# 328P_ISP.net
KiCad netlist of a schematic drawn in EAGLE
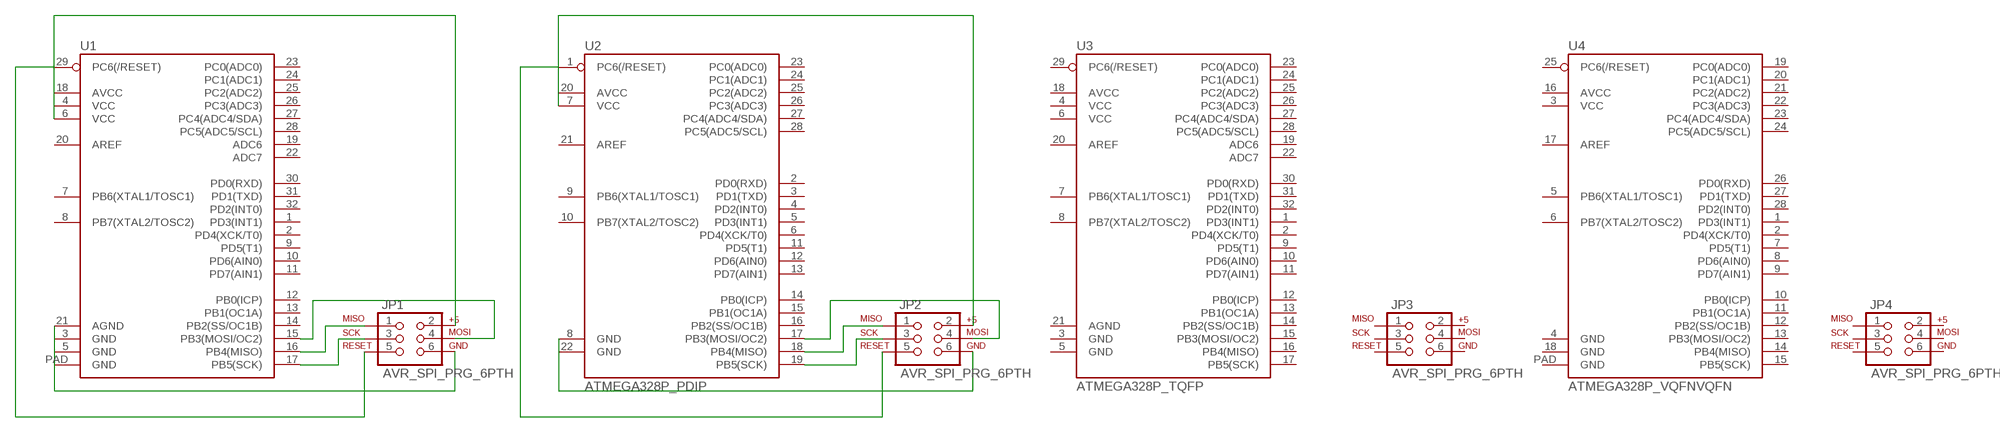
[diagram p0: schematic, sheet 1]

(export (version "E")
  (design (tool "Eeschema 10.0.6"))
  (components
    (comp (ref "JP1")
      (value "AVR_SPI_PRG_6PTH")
      (footprint "eagle-import:2X3")
      (libsource (lib "eagle-import") (part "AVR_SPI_PRG_6PTH"))
    )
    (comp (ref "JP2")
      (value "AVR_SPI_PRG_6PTH")
      (footprint "eagle-import:2X3")
      (libsource (lib "eagle-import") (part "AVR_SPI_PRG_6PTH"))
    )
    (comp (ref "JP3")
      (value "AVR_SPI_PRG_6PTH")
      (footprint "eagle-import:2X3")
      (libsource (lib "eagle-import") (part "AVR_SPI_PRG_6PTH"))
    )
    (comp (ref "JP4")
      (value "AVR_SPI_PRG_6PTH")
      (footprint "eagle-import:2X3")
      (libsource (lib "eagle-import") (part "AVR_SPI_PRG_6PTH"))
    )
    (comp (ref "U1")
      (value "ATMEGA328P_MLFMLF32")
      (footprint "eagle-import:MLF32-PAD")
      (libsource (lib "eagle-import") (part "ATMEGA328P_MLFMLF32"))
    )
    (comp (ref "U2")
      (value "ATMEGA328P_PDIP")
      (footprint "eagle-import:DIL28-3")
      (libsource (lib "eagle-import") (part "ATMEGA328P_PDIP"))
    )
    (comp (ref "U3")
      (value "ATMEGA328P_TQFP")
      (footprint "eagle-import:TQFP32-08")
      (libsource (lib "eagle-import") (part "ATMEGA328P_TQFP"))
    )
    (comp (ref "U4")
      (value "ATMEGA328P_VQFNVQFN")
      (footprint "eagle-import:VQFN-28")
      (libsource (lib "eagle-import") (part "ATMEGA328P_VQFNVQFN"))
    )
  )
  (nets
    (net (code "1") (name "Net-(JP2-Pad6)") (class "Default")
      (node (ref "JP2") (pin "6") (pinfunction "6_6") (pintype "passive"))
      (node (ref "U2") (pin "22") (pinfunction "GND_22") (pintype "bidirectional"))
      (node (ref "U2") (pin "8") (pinfunction "GND_8") (pintype "bidirectional"))
    )
    (net (code "2") (name "Net-(U1-AGND)") (class "Default")
      (node (ref "JP1") (pin "6") (pinfunction "6_6") (pintype "passive"))
      (node (ref "U1") (pin "21") (pinfunction "AGND_21") (pintype "bidirectional"))
      (node (ref "U1") (pin "3") (pinfunction "GND_3") (pintype "bidirectional"))
      (node (ref "U1") (pin "5") (pinfunction "GND_5") (pintype "bidirectional"))
      (node (ref "U1") (pin "PAD") (pinfunction "GND_PAD") (pintype "bidirectional"))
    )
    (net (code "3") (name "Net-(U1-AVCC)") (class "Default")
      (node (ref "JP1") (pin "2") (pinfunction "2_2") (pintype "passive"))
      (node (ref "U1") (pin "18") (pinfunction "AVCC_18") (pintype "bidirectional"))
      (node (ref "U1") (pin "4") (pinfunction "VCC_4") (pintype "bidirectional"))
      (node (ref "U1") (pin "6") (pinfunction "VCC_6") (pintype "bidirectional"))
    )
    (net (code "4") (name "Net-(U1-PB3(MOSI{slash}OC2))") (class "Default")
      (node (ref "JP1") (pin "4") (pinfunction "4_4") (pintype "passive"))
      (node (ref "U1") (pin "15") (pinfunction "PB3(MOSI/OC2)_15") (pintype "bidirectional"))
    )
    (net (code "5") (name "Net-(U1-PB4(MISO))") (class "Default")
      (node (ref "JP1") (pin "1") (pinfunction "1_1") (pintype "passive"))
      (node (ref "U1") (pin "16") (pinfunction "PB4(MISO)_16") (pintype "bidirectional"))
    )
    (net (code "6") (name "Net-(U1-PB5(SCK))") (class "Default")
      (node (ref "JP1") (pin "3") (pinfunction "3_3") (pintype "passive"))
      (node (ref "U1") (pin "17") (pinfunction "PB5(SCK)_17") (pintype "bidirectional"))
    )
    (net (code "7") (name "Net-(U1-PC6({slash}RESET))") (class "Default")
      (node (ref "JP1") (pin "5") (pinfunction "5_5") (pintype "passive"))
      (node (ref "U1") (pin "29") (pinfunction "PC6(/RESET)_29") (pintype "bidirectional"))
    )
    (net (code "8") (name "Net-(U2-AVCC)") (class "Default")
      (node (ref "JP2") (pin "2") (pinfunction "2_2") (pintype "passive"))
      (node (ref "U2") (pin "20") (pinfunction "AVCC_20") (pintype "bidirectional"))
      (node (ref "U2") (pin "7") (pinfunction "VCC_7") (pintype "bidirectional"))
    )
    (net (code "9") (name "Net-(U2-PB3(MOSI{slash}OC2))") (class "Default")
      (node (ref "JP2") (pin "4") (pinfunction "4_4") (pintype "passive"))
      (node (ref "U2") (pin "17") (pinfunction "PB3(MOSI/OC2)_17") (pintype "bidirectional"))
    )
    (net (code "10") (name "Net-(U2-PB4(MISO))") (class "Default")
      (node (ref "JP2") (pin "1") (pinfunction "1_1") (pintype "passive"))
      (node (ref "U2") (pin "18") (pinfunction "PB4(MISO)_18") (pintype "bidirectional"))
    )
    (net (code "11") (name "Net-(U2-PB5(SCK))") (class "Default")
      (node (ref "JP2") (pin "3") (pinfunction "3_3") (pintype "passive"))
      (node (ref "U2") (pin "19") (pinfunction "PB5(SCK)_19") (pintype "bidirectional"))
    )
    (net (code "12") (name "Net-(U2-PC6({slash}RESET))") (class "Default")
      (node (ref "JP2") (pin "5") (pinfunction "5_5") (pintype "passive"))
      (node (ref "U2") (pin "1") (pinfunction "PC6(/RESET)_1") (pintype "bidirectional"))
    )
    (net (code "13") (name "unconnected-(JP3-Pad1)") (class "Default")
      (node (ref "JP3") (pin "1") (pinfunction "1_1") (pintype "passive"))
    )
    (net (code "14") (name "unconnected-(JP3-Pad2)") (class "Default")
      (node (ref "JP3") (pin "2") (pinfunction "2_2") (pintype "passive"))
    )
    (net (code "15") (name "unconnected-(JP3-Pad3)") (class "Default")
      (node (ref "JP3") (pin "3") (pinfunction "3_3") (pintype "passive"))
    )
    (net (code "16") (name "unconnected-(JP3-Pad4)") (class "Default")
      (node (ref "JP3") (pin "4") (pinfunction "4_4") (pintype "passive"))
    )
    (net (code "17") (name "unconnected-(JP3-Pad5)") (class "Default")
      (node (ref "JP3") (pin "5") (pinfunction "5_5") (pintype "passive"))
    )
    (net (code "18") (name "unconnected-(JP3-Pad6)") (class "Default")
      (node (ref "JP3") (pin "6") (pinfunction "6_6") (pintype "passive"))
    )
    (net (code "19") (name "unconnected-(JP4-Pad1)") (class "Default")
      (node (ref "JP4") (pin "1") (pinfunction "1_1") (pintype "passive"))
    )
    (net (code "20") (name "unconnected-(JP4-Pad2)") (class "Default")
      (node (ref "JP4") (pin "2") (pinfunction "2_2") (pintype "passive"))
    )
    (net (code "21") (name "unconnected-(JP4-Pad3)") (class "Default")
      (node (ref "JP4") (pin "3") (pinfunction "3_3") (pintype "passive"))
    )
    (net (code "22") (name "unconnected-(JP4-Pad4)") (class "Default")
      (node (ref "JP4") (pin "4") (pinfunction "4_4") (pintype "passive"))
    )
    (net (code "23") (name "unconnected-(JP4-Pad5)") (class "Default")
      (node (ref "JP4") (pin "5") (pinfunction "5_5") (pintype "passive"))
    )
    (net (code "24") (name "unconnected-(JP4-Pad6)") (class "Default")
      (node (ref "JP4") (pin "6") (pinfunction "6_6") (pintype "passive"))
    )
    (net (code "25") (name "unconnected-(U1-ADC6-Pad19)") (class "Default")
      (node (ref "U1") (pin "19") (pinfunction "ADC6_19") (pintype "bidirectional"))
    )
    (net (code "26") (name "unconnected-(U1-ADC7-Pad22)") (class "Default")
      (node (ref "U1") (pin "22") (pinfunction "ADC7_22") (pintype "bidirectional"))
    )
    (net (code "27") (name "unconnected-(U1-AREF-Pad20)") (class "Default")
      (node (ref "U1") (pin "20") (pinfunction "AREF_20") (pintype "bidirectional"))
    )
    (net (code "28") (name "unconnected-(U1-PB0(ICP)-Pad12)") (class "Default")
      (node (ref "U1") (pin "12") (pinfunction "PB0(ICP)_12") (pintype "bidirectional"))
    )
    (net (code "29") (name "unconnected-(U1-PB1(OC1A)-Pad13)") (class "Default")
      (node (ref "U1") (pin "13") (pinfunction "PB1(OC1A)_13") (pintype "bidirectional"))
    )
    (net (code "30") (name "unconnected-(U1-PB2(SS{slash}OC1B)-Pad14)") (class "Default")
      (node (ref "U1") (pin "14") (pinfunction "PB2(SS/OC1B)_14") (pintype "bidirectional"))
    )
    (net (code "31") (name "unconnected-(U1-PB6(XTAL1{slash}TOSC1)-Pad7)") (class "Default")
      (node (ref "U1") (pin "7") (pinfunction "PB6(XTAL1/TOSC1)_7") (pintype "bidirectional"))
    )
    (net (code "32") (name "unconnected-(U1-PB7(XTAL2{slash}TOSC2)-Pad8)") (class "Default")
      (node (ref "U1") (pin "8") (pinfunction "PB7(XTAL2/TOSC2)_8") (pintype "bidirectional"))
    )
    (net (code "33") (name "unconnected-(U1-PC0(ADC0)-Pad23)") (class "Default")
      (node (ref "U1") (pin "23") (pinfunction "PC0(ADC0)_23") (pintype "bidirectional"))
    )
    (net (code "34") (name "unconnected-(U1-PC1(ADC1)-Pad24)") (class "Default")
      (node (ref "U1") (pin "24") (pinfunction "PC1(ADC1)_24") (pintype "bidirectional"))
    )
    (net (code "35") (name "unconnected-(U1-PC2(ADC2)-Pad25)") (class "Default")
      (node (ref "U1") (pin "25") (pinfunction "PC2(ADC2)_25") (pintype "bidirectional"))
    )
    (net (code "36") (name "unconnected-(U1-PC3(ADC3)-Pad26)") (class "Default")
      (node (ref "U1") (pin "26") (pinfunction "PC3(ADC3)_26") (pintype "bidirectional"))
    )
    (net (code "37") (name "unconnected-(U1-PC4(ADC4{slash}SDA)-Pad27)") (class "Default")
      (node (ref "U1") (pin "27") (pinfunction "PC4(ADC4/SDA)_27") (pintype "bidirectional"))
    )
    (net (code "38") (name "unconnected-(U1-PC5(ADC5{slash}SCL)-Pad28)") (class "Default")
      (node (ref "U1") (pin "28") (pinfunction "PC5(ADC5/SCL)_28") (pintype "bidirectional"))
    )
    (net (code "39") (name "unconnected-(U1-PD0(RXD)-Pad30)") (class "Default")
      (node (ref "U1") (pin "30") (pinfunction "PD0(RXD)_30") (pintype "bidirectional"))
    )
    (net (code "40") (name "unconnected-(U1-PD1(TXD)-Pad31)") (class "Default")
      (node (ref "U1") (pin "31") (pinfunction "PD1(TXD)_31") (pintype "bidirectional"))
    )
    (net (code "41") (name "unconnected-(U1-PD2(INT0)-Pad32)") (class "Default")
      (node (ref "U1") (pin "32") (pinfunction "PD2(INT0)_32") (pintype "bidirectional"))
    )
    (net (code "42") (name "unconnected-(U1-PD3(INT1)-Pad1)") (class "Default")
      (node (ref "U1") (pin "1") (pinfunction "PD3(INT1)_1") (pintype "bidirectional"))
    )
    (net (code "43") (name "unconnected-(U1-PD4(XCK{slash}T0)-Pad2)") (class "Default")
      (node (ref "U1") (pin "2") (pinfunction "PD4(XCK/T0)_2") (pintype "bidirectional"))
    )
    (net (code "44") (name "unconnected-(U1-PD5(T1)-Pad9)") (class "Default")
      (node (ref "U1") (pin "9") (pinfunction "PD5(T1)_9") (pintype "bidirectional"))
    )
    (net (code "45") (name "unconnected-(U1-PD6(AIN0)-Pad10)") (class "Default")
      (node (ref "U1") (pin "10") (pinfunction "PD6(AIN0)_10") (pintype "bidirectional"))
    )
    (net (code "46") (name "unconnected-(U1-PD7(AIN1)-Pad11)") (class "Default")
      (node (ref "U1") (pin "11") (pinfunction "PD7(AIN1)_11") (pintype "bidirectional"))
    )
    (net (code "47") (name "unconnected-(U2-AREF-Pad21)") (class "Default")
      (node (ref "U2") (pin "21") (pinfunction "AREF_21") (pintype "bidirectional"))
    )
    (net (code "48") (name "unconnected-(U2-PB0(ICP)-Pad14)") (class "Default")
      (node (ref "U2") (pin "14") (pinfunction "PB0(ICP)_14") (pintype "bidirectional"))
    )
    (net (code "49") (name "unconnected-(U2-PB1(OC1A)-Pad15)") (class "Default")
      (node (ref "U2") (pin "15") (pinfunction "PB1(OC1A)_15") (pintype "bidirectional"))
    )
    (net (code "50") (name "unconnected-(U2-PB2(SS{slash}OC1B)-Pad16)") (class "Default")
      (node (ref "U2") (pin "16") (pinfunction "PB2(SS/OC1B)_16") (pintype "bidirectional"))
    )
    (net (code "51") (name "unconnected-(U2-PB6(XTAL1{slash}TOSC1)-Pad9)") (class "Default")
      (node (ref "U2") (pin "9") (pinfunction "PB6(XTAL1/TOSC1)_9") (pintype "bidirectional"))
    )
    (net (code "52") (name "unconnected-(U2-PB7(XTAL2{slash}TOSC2)-Pad10)") (class "Default")
      (node (ref "U2") (pin "10") (pinfunction "PB7(XTAL2/TOSC2)_10") (pintype "bidirectional"))
    )
    (net (code "53") (name "unconnected-(U2-PC0(ADC0)-Pad23)") (class "Default")
      (node (ref "U2") (pin "23") (pinfunction "PC0(ADC0)_23") (pintype "bidirectional"))
    )
    (net (code "54") (name "unconnected-(U2-PC1(ADC1)-Pad24)") (class "Default")
      (node (ref "U2") (pin "24") (pinfunction "PC1(ADC1)_24") (pintype "bidirectional"))
    )
    (net (code "55") (name "unconnected-(U2-PC2(ADC2)-Pad25)") (class "Default")
      (node (ref "U2") (pin "25") (pinfunction "PC2(ADC2)_25") (pintype "bidirectional"))
    )
    (net (code "56") (name "unconnected-(U2-PC3(ADC3)-Pad26)") (class "Default")
      (node (ref "U2") (pin "26") (pinfunction "PC3(ADC3)_26") (pintype "bidirectional"))
    )
    (net (code "57") (name "unconnected-(U2-PC4(ADC4{slash}SDA)-Pad27)") (class "Default")
      (node (ref "U2") (pin "27") (pinfunction "PC4(ADC4/SDA)_27") (pintype "bidirectional"))
    )
    (net (code "58") (name "unconnected-(U2-PC5(ADC5{slash}SCL)-Pad28)") (class "Default")
      (node (ref "U2") (pin "28") (pinfunction "PC5(ADC5/SCL)_28") (pintype "bidirectional"))
    )
    (net (code "59") (name "unconnected-(U2-PD0(RXD)-Pad2)") (class "Default")
      (node (ref "U2") (pin "2") (pinfunction "PD0(RXD)_2") (pintype "bidirectional"))
    )
    (net (code "60") (name "unconnected-(U2-PD1(TXD)-Pad3)") (class "Default")
      (node (ref "U2") (pin "3") (pinfunction "PD1(TXD)_3") (pintype "bidirectional"))
    )
    (net (code "61") (name "unconnected-(U2-PD2(INT0)-Pad4)") (class "Default")
      (node (ref "U2") (pin "4") (pinfunction "PD2(INT0)_4") (pintype "bidirectional"))
    )
    (net (code "62") (name "unconnected-(U2-PD3(INT1)-Pad5)") (class "Default")
      (node (ref "U2") (pin "5") (pinfunction "PD3(INT1)_5") (pintype "bidirectional"))
    )
    (net (code "63") (name "unconnected-(U2-PD4(XCK{slash}T0)-Pad6)") (class "Default")
      (node (ref "U2") (pin "6") (pinfunction "PD4(XCK/T0)_6") (pintype "bidirectional"))
    )
    (net (code "64") (name "unconnected-(U2-PD5(T1)-Pad11)") (class "Default")
      (node (ref "U2") (pin "11") (pinfunction "PD5(T1)_11") (pintype "bidirectional"))
    )
    (net (code "65") (name "unconnected-(U2-PD6(AIN0)-Pad12)") (class "Default")
      (node (ref "U2") (pin "12") (pinfunction "PD6(AIN0)_12") (pintype "bidirectional"))
    )
    (net (code "66") (name "unconnected-(U2-PD7(AIN1)-Pad13)") (class "Default")
      (node (ref "U2") (pin "13") (pinfunction "PD7(AIN1)_13") (pintype "bidirectional"))
    )
    (net (code "67") (name "unconnected-(U3-ADC6-Pad19)") (class "Default")
      (node (ref "U3") (pin "19") (pinfunction "ADC6_19") (pintype "bidirectional"))
    )
    (net (code "68") (name "unconnected-(U3-ADC7-Pad22)") (class "Default")
      (node (ref "U3") (pin "22") (pinfunction "ADC7_22") (pintype "bidirectional"))
    )
    (net (code "69") (name "unconnected-(U3-AGND-Pad21)") (class "Default")
      (node (ref "U3") (pin "21") (pinfunction "AGND_21") (pintype "bidirectional"))
    )
    (net (code "70") (name "unconnected-(U3-AREF-Pad20)") (class "Default")
      (node (ref "U3") (pin "20") (pinfunction "AREF_20") (pintype "bidirectional"))
    )
    (net (code "71") (name "unconnected-(U3-AVCC-Pad18)") (class "Default")
      (node (ref "U3") (pin "18") (pinfunction "AVCC_18") (pintype "bidirectional"))
    )
    (net (code "72") (name "unconnected-(U3-GND-Pad3)") (class "Default")
      (node (ref "U3") (pin "3") (pinfunction "GND_3") (pintype "bidirectional"))
    )
    (net (code "73") (name "unconnected-(U3-GND-Pad5)") (class "Default")
      (node (ref "U3") (pin "5") (pinfunction "GND_5") (pintype "bidirectional"))
    )
    (net (code "74") (name "unconnected-(U3-PB0(ICP)-Pad12)") (class "Default")
      (node (ref "U3") (pin "12") (pinfunction "PB0(ICP)_12") (pintype "bidirectional"))
    )
    (net (code "75") (name "unconnected-(U3-PB1(OC1A)-Pad13)") (class "Default")
      (node (ref "U3") (pin "13") (pinfunction "PB1(OC1A)_13") (pintype "bidirectional"))
    )
    (net (code "76") (name "unconnected-(U3-PB2(SS{slash}OC1B)-Pad14)") (class "Default")
      (node (ref "U3") (pin "14") (pinfunction "PB2(SS/OC1B)_14") (pintype "bidirectional"))
    )
    (net (code "77") (name "unconnected-(U3-PB3(MOSI{slash}OC2)-Pad15)") (class "Default")
      (node (ref "U3") (pin "15") (pinfunction "PB3(MOSI/OC2)_15") (pintype "bidirectional"))
    )
    (net (code "78") (name "unconnected-(U3-PB4(MISO)-Pad16)") (class "Default")
      (node (ref "U3") (pin "16") (pinfunction "PB4(MISO)_16") (pintype "bidirectional"))
    )
    (net (code "79") (name "unconnected-(U3-PB5(SCK)-Pad17)") (class "Default")
      (node (ref "U3") (pin "17") (pinfunction "PB5(SCK)_17") (pintype "bidirectional"))
    )
    (net (code "80") (name "unconnected-(U3-PB6(XTAL1{slash}TOSC1)-Pad7)") (class "Default")
      (node (ref "U3") (pin "7") (pinfunction "PB6(XTAL1/TOSC1)_7") (pintype "bidirectional"))
    )
    (net (code "81") (name "unconnected-(U3-PB7(XTAL2{slash}TOSC2)-Pad8)") (class "Default")
      (node (ref "U3") (pin "8") (pinfunction "PB7(XTAL2/TOSC2)_8") (pintype "bidirectional"))
    )
    (net (code "82") (name "unconnected-(U3-PC0(ADC0)-Pad23)") (class "Default")
      (node (ref "U3") (pin "23") (pinfunction "PC0(ADC0)_23") (pintype "bidirectional"))
    )
    (net (code "83") (name "unconnected-(U3-PC1(ADC1)-Pad24)") (class "Default")
      (node (ref "U3") (pin "24") (pinfunction "PC1(ADC1)_24") (pintype "bidirectional"))
    )
    (net (code "84") (name "unconnected-(U3-PC2(ADC2)-Pad25)") (class "Default")
      (node (ref "U3") (pin "25") (pinfunction "PC2(ADC2)_25") (pintype "bidirectional"))
    )
    (net (code "85") (name "unconnected-(U3-PC3(ADC3)-Pad26)") (class "Default")
      (node (ref "U3") (pin "26") (pinfunction "PC3(ADC3)_26") (pintype "bidirectional"))
    )
    (net (code "86") (name "unconnected-(U3-PC4(ADC4{slash}SDA)-Pad27)") (class "Default")
      (node (ref "U3") (pin "27") (pinfunction "PC4(ADC4/SDA)_27") (pintype "bidirectional"))
    )
    (net (code "87") (name "unconnected-(U3-PC5(ADC5{slash}SCL)-Pad28)") (class "Default")
      (node (ref "U3") (pin "28") (pinfunction "PC5(ADC5/SCL)_28") (pintype "bidirectional"))
    )
    (net (code "88") (name "unconnected-(U3-PC6({slash}RESET)-Pad29)") (class "Default")
      (node (ref "U3") (pin "29") (pinfunction "PC6(/RESET)_29") (pintype "bidirectional"))
    )
    (net (code "89") (name "unconnected-(U3-PD0(RXD)-Pad30)") (class "Default")
      (node (ref "U3") (pin "30") (pinfunction "PD0(RXD)_30") (pintype "bidirectional"))
    )
    (net (code "90") (name "unconnected-(U3-PD1(TXD)-Pad31)") (class "Default")
      (node (ref "U3") (pin "31") (pinfunction "PD1(TXD)_31") (pintype "bidirectional"))
    )
    (net (code "91") (name "unconnected-(U3-PD2(INT0)-Pad32)") (class "Default")
      (node (ref "U3") (pin "32") (pinfunction "PD2(INT0)_32") (pintype "bidirectional"))
    )
    (net (code "92") (name "unconnected-(U3-PD3(INT1)-Pad1)") (class "Default")
      (node (ref "U3") (pin "1") (pinfunction "PD3(INT1)_1") (pintype "bidirectional"))
    )
    (net (code "93") (name "unconnected-(U3-PD4(XCK{slash}T0)-Pad2)") (class "Default")
      (node (ref "U3") (pin "2") (pinfunction "PD4(XCK/T0)_2") (pintype "bidirectional"))
    )
    (net (code "94") (name "unconnected-(U3-PD5(T1)-Pad9)") (class "Default")
      (node (ref "U3") (pin "9") (pinfunction "PD5(T1)_9") (pintype "bidirectional"))
    )
    (net (code "95") (name "unconnected-(U3-PD6(AIN0)-Pad10)") (class "Default")
      (node (ref "U3") (pin "10") (pinfunction "PD6(AIN0)_10") (pintype "bidirectional"))
    )
    (net (code "96") (name "unconnected-(U3-PD7(AIN1)-Pad11)") (class "Default")
      (node (ref "U3") (pin "11") (pinfunction "PD7(AIN1)_11") (pintype "bidirectional"))
    )
    (net (code "97") (name "unconnected-(U3-VCC-Pad4)") (class "Default")
      (node (ref "U3") (pin "4") (pinfunction "VCC_4") (pintype "bidirectional"))
    )
    (net (code "98") (name "unconnected-(U3-VCC-Pad6)") (class "Default")
      (node (ref "U3") (pin "6") (pinfunction "VCC_6") (pintype "bidirectional"))
    )
    (net (code "99") (name "unconnected-(U4-AREF-Pad17)") (class "Default")
      (node (ref "U4") (pin "17") (pinfunction "AREF_17") (pintype "bidirectional"))
    )
    (net (code "100") (name "unconnected-(U4-AVCC-Pad16)") (class "Default")
      (node (ref "U4") (pin "16") (pinfunction "AVCC_16") (pintype "bidirectional"))
    )
    (net (code "101") (name "unconnected-(U4-GND-Pad4)") (class "Default")
      (node (ref "U4") (pin "4") (pinfunction "GND_4") (pintype "bidirectional"))
    )
    (net (code "102") (name "unconnected-(U4-GND-Pad18)") (class "Default")
      (node (ref "U4") (pin "18") (pinfunction "GND_18") (pintype "bidirectional"))
    )
    (net (code "103") (name "unconnected-(U4-GND-PadPAD)") (class "Default")
      (node (ref "U4") (pin "PAD") (pinfunction "GND_PAD") (pintype "bidirectional"))
    )
    (net (code "104") (name "unconnected-(U4-PB0(ICP)-Pad10)") (class "Default")
      (node (ref "U4") (pin "10") (pinfunction "PB0(ICP)_10") (pintype "bidirectional"))
    )
    (net (code "105") (name "unconnected-(U4-PB1(OC1A)-Pad11)") (class "Default")
      (node (ref "U4") (pin "11") (pinfunction "PB1(OC1A)_11") (pintype "bidirectional"))
    )
    (net (code "106") (name "unconnected-(U4-PB2(SS{slash}OC1B)-Pad12)") (class "Default")
      (node (ref "U4") (pin "12") (pinfunction "PB2(SS/OC1B)_12") (pintype "bidirectional"))
    )
    (net (code "107") (name "unconnected-(U4-PB3(MOSI{slash}OC2)-Pad13)") (class "Default")
      (node (ref "U4") (pin "13") (pinfunction "PB3(MOSI/OC2)_13") (pintype "bidirectional"))
    )
    (net (code "108") (name "unconnected-(U4-PB4(MISO)-Pad14)") (class "Default")
      (node (ref "U4") (pin "14") (pinfunction "PB4(MISO)_14") (pintype "bidirectional"))
    )
    (net (code "109") (name "unconnected-(U4-PB5(SCK)-Pad15)") (class "Default")
      (node (ref "U4") (pin "15") (pinfunction "PB5(SCK)_15") (pintype "bidirectional"))
    )
    (net (code "110") (name "unconnected-(U4-PB6(XTAL1{slash}TOSC1)-Pad5)") (class "Default")
      (node (ref "U4") (pin "5") (pinfunction "PB6(XTAL1/TOSC1)_5") (pintype "bidirectional"))
    )
    (net (code "111") (name "unconnected-(U4-PB7(XTAL2{slash}TOSC2)-Pad6)") (class "Default")
      (node (ref "U4") (pin "6") (pinfunction "PB7(XTAL2/TOSC2)_6") (pintype "bidirectional"))
    )
    (net (code "112") (name "unconnected-(U4-PC0(ADC0)-Pad19)") (class "Default")
      (node (ref "U4") (pin "19") (pinfunction "PC0(ADC0)_19") (pintype "bidirectional"))
    )
    (net (code "113") (name "unconnected-(U4-PC1(ADC1)-Pad20)") (class "Default")
      (node (ref "U4") (pin "20") (pinfunction "PC1(ADC1)_20") (pintype "bidirectional"))
    )
    (net (code "114") (name "unconnected-(U4-PC2(ADC2)-Pad21)") (class "Default")
      (node (ref "U4") (pin "21") (pinfunction "PC2(ADC2)_21") (pintype "bidirectional"))
    )
    (net (code "115") (name "unconnected-(U4-PC3(ADC3)-Pad22)") (class "Default")
      (node (ref "U4") (pin "22") (pinfunction "PC3(ADC3)_22") (pintype "bidirectional"))
    )
    (net (code "116") (name "unconnected-(U4-PC4(ADC4{slash}SDA)-Pad23)") (class "Default")
      (node (ref "U4") (pin "23") (pinfunction "PC4(ADC4/SDA)_23") (pintype "bidirectional"))
    )
    (net (code "117") (name "unconnected-(U4-PC5(ADC5{slash}SCL)-Pad24)") (class "Default")
      (node (ref "U4") (pin "24") (pinfunction "PC5(ADC5/SCL)_24") (pintype "bidirectional"))
    )
    (net (code "118") (name "unconnected-(U4-PC6({slash}RESET)-Pad25)") (class "Default")
      (node (ref "U4") (pin "25") (pinfunction "PC6(/RESET)_25") (pintype "bidirectional"))
    )
    (net (code "119") (name "unconnected-(U4-PD0(RXD)-Pad26)") (class "Default")
      (node (ref "U4") (pin "26") (pinfunction "PD0(RXD)_26") (pintype "bidirectional"))
    )
    (net (code "120") (name "unconnected-(U4-PD1(TXD)-Pad27)") (class "Default")
      (node (ref "U4") (pin "27") (pinfunction "PD1(TXD)_27") (pintype "bidirectional"))
    )
    (net (code "121") (name "unconnected-(U4-PD2(INT0)-Pad28)") (class "Default")
      (node (ref "U4") (pin "28") (pinfunction "PD2(INT0)_28") (pintype "bidirectional"))
    )
    (net (code "122") (name "unconnected-(U4-PD3(INT1)-Pad1)") (class "Default")
      (node (ref "U4") (pin "1") (pinfunction "PD3(INT1)_1") (pintype "bidirectional"))
    )
    (net (code "123") (name "unconnected-(U4-PD4(XCK{slash}T0)-Pad2)") (class "Default")
      (node (ref "U4") (pin "2") (pinfunction "PD4(XCK/T0)_2") (pintype "bidirectional"))
    )
    (net (code "124") (name "unconnected-(U4-PD5(T1)-Pad7)") (class "Default")
      (node (ref "U4") (pin "7") (pinfunction "PD5(T1)_7") (pintype "bidirectional"))
    )
    (net (code "125") (name "unconnected-(U4-PD6(AIN0)-Pad8)") (class "Default")
      (node (ref "U4") (pin "8") (pinfunction "PD6(AIN0)_8") (pintype "bidirectional"))
    )
    (net (code "126") (name "unconnected-(U4-PD7(AIN1)-Pad9)") (class "Default")
      (node (ref "U4") (pin "9") (pinfunction "PD7(AIN1)_9") (pintype "bidirectional"))
    )
    (net (code "127") (name "unconnected-(U4-VCC-Pad3)") (class "Default")
      (node (ref "U4") (pin "3") (pinfunction "VCC_3") (pintype "bidirectional"))
    )
  )
)
